# 1_-POWER.net
KiCad netlist of a schematic drawn in Altium Designer
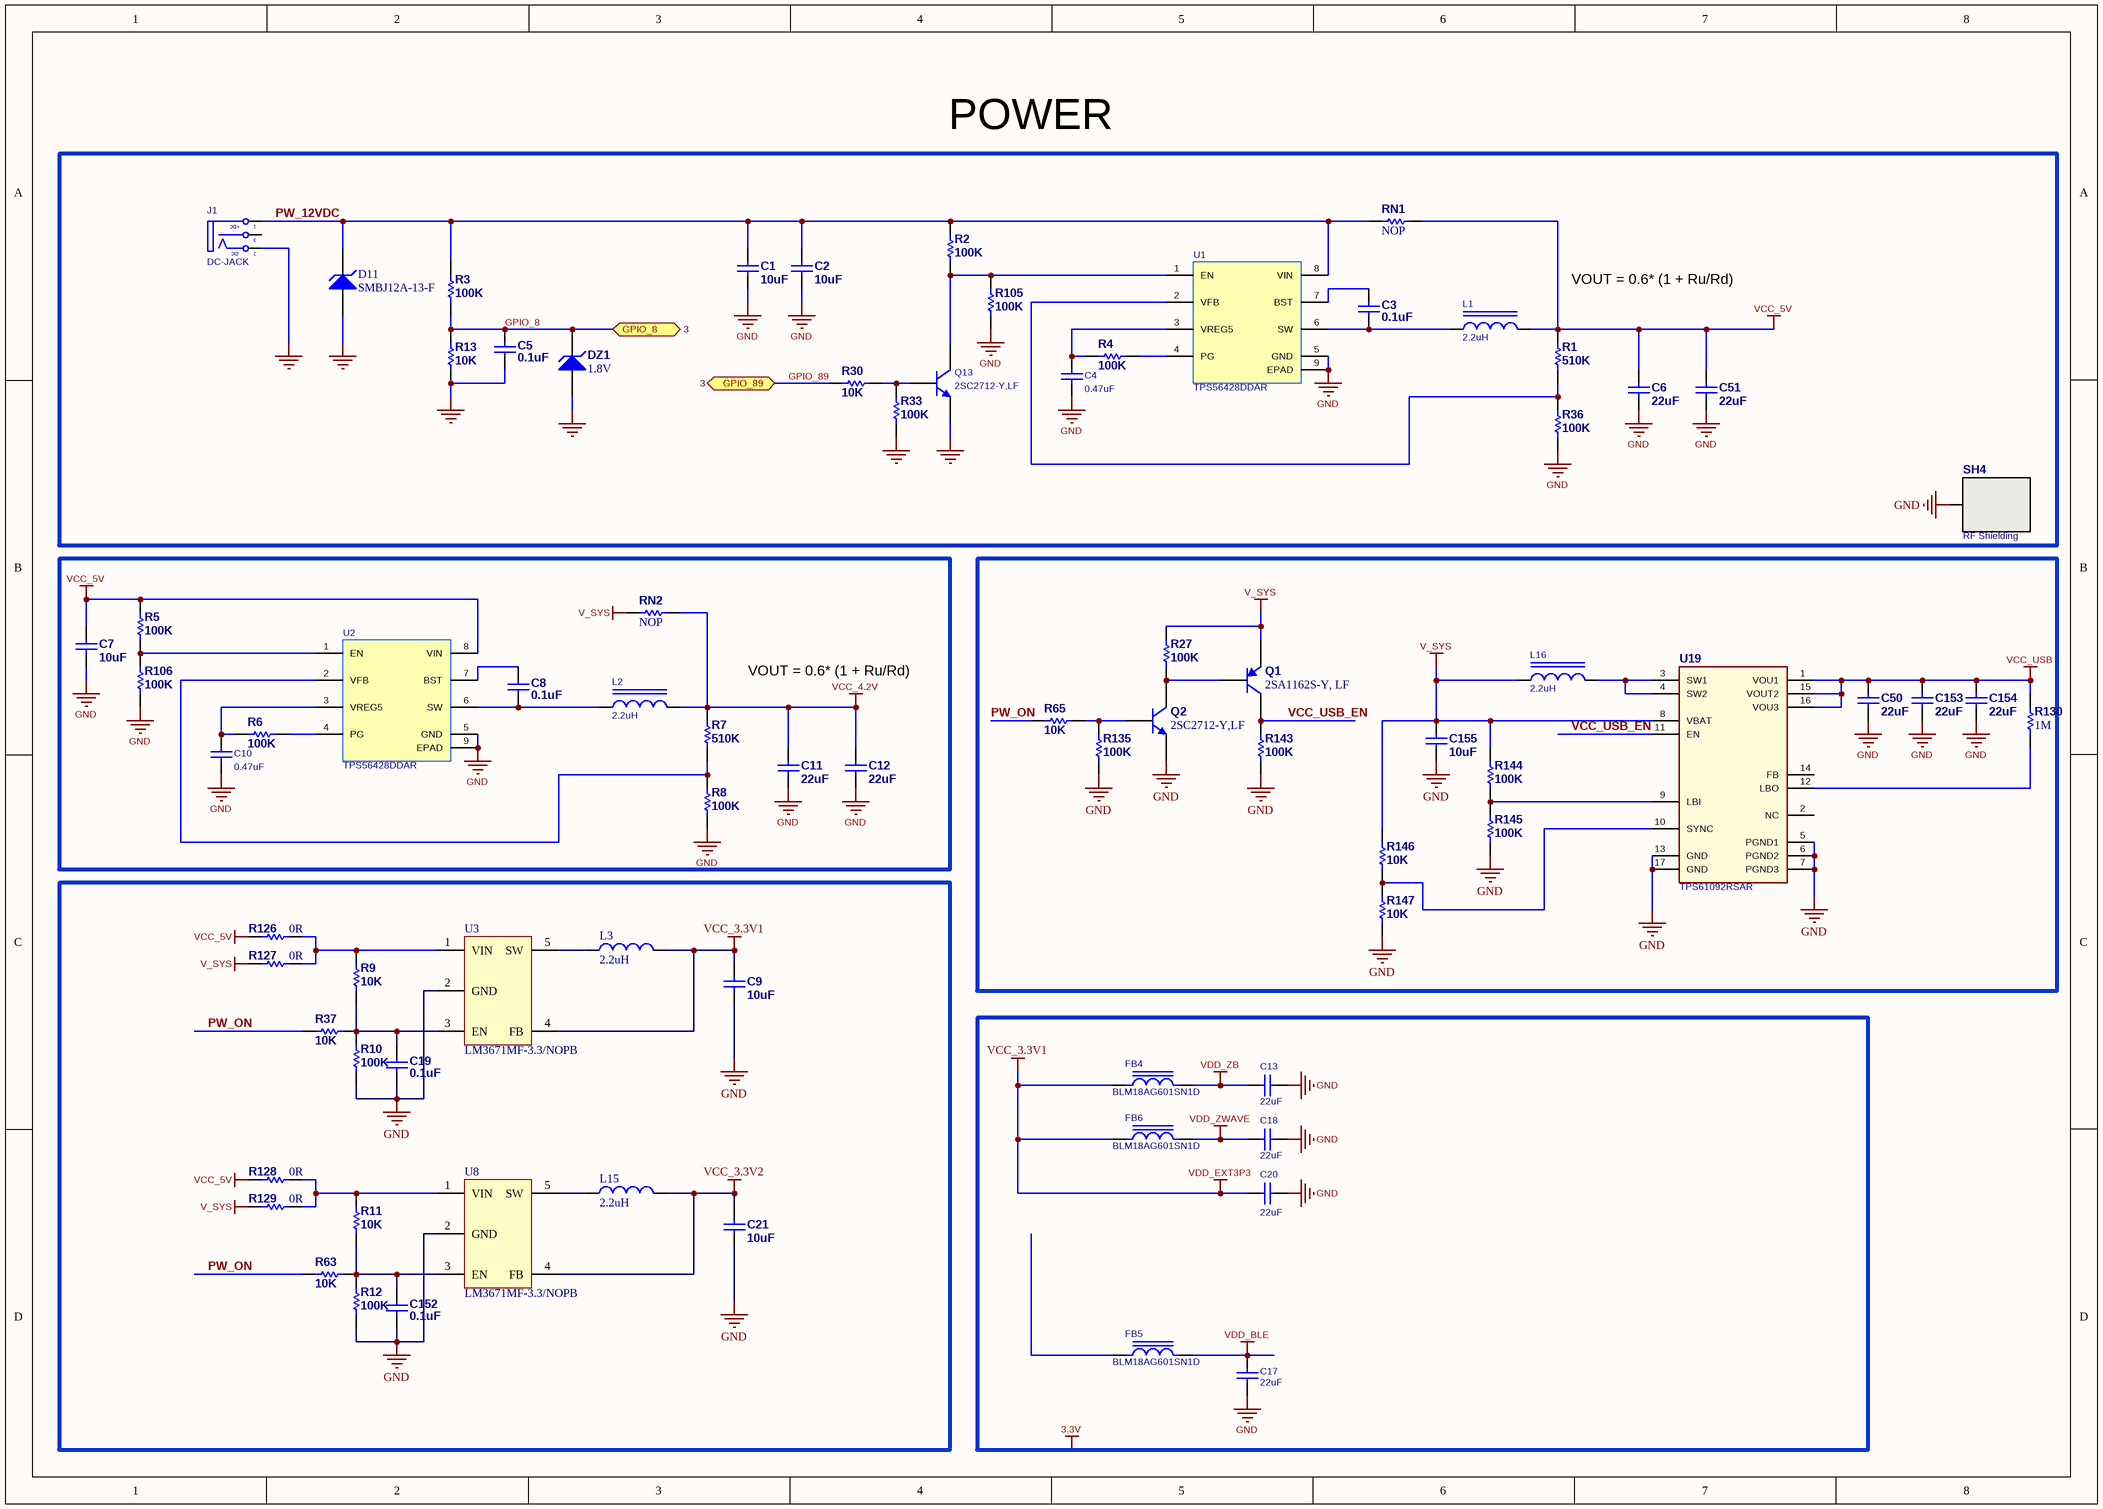
[diagram p0: [1]-POWER.SchDoc]

(export (version "E")
  (design (tool "Eeschema 10.0.6"))
  (components
    (comp (ref "C1")
      (value "TMK212BBJ106KG-T")
      (footprint "C0805")
      (description "CAP, CERM, 10uF, 25V, +/-10%, X5R, 0402")
      (fields
        (field (name "LUMI PART") "CAP_10uF_0805")
        (field (name "MANUFACTURER") "Taiyo Yuden")
        (field (name "CAPACITANCE") "10uF")
      )
      (libsource (lib "EFL_AltiumLib") (part "CAP_10uF_0805"))
    )
    (comp (ref "C2")
      (value "TMK212BBJ106KG-T")
      (footprint "C0805")
      (description "CAP, CERM, 10uF, 25V, +/-10%, X5R, 0402")
      (fields
        (field (name "LUMI PART") "CAP_10uF_0805")
        (field (name "MANUFACTURER") "Taiyo Yuden")
        (field (name "CAPACITANCE") "10uF")
      )
      (libsource (lib "EFL_AltiumLib") (part "CAP_10uF_0805"))
    )
    (comp (ref "C3")
      (value "0603B104K500CT")
      (footprint "C0603")
      (description "CAP, CERM, 0.1uF, 50V, +/-10%, X7R, 0603")
      (fields
        (field (name "LUMI PART") "CAP_104_0603")
        (field (name "MANUFACTURER") "Walsin")
        (field (name "CAPACITANCE") "0.1uF")
      )
      (libsource (lib "LumiLib-CAPACITOR") (part "CERM_0.1uF_0603"))
    )
    (comp (ref "C4")
      (value "0603B474K500CT")
      (footprint "C0603")
      (description "CAP, CERM, 0.47uF, 50V, +/-10%, X7R, 0603")
      (fields
        (field (name "LUMI PART") "CAP_0.47uF_0603")
        (field (name "MANUFACTURER") "Walsin")
        (field (name "CAPACITANCE") "0.47uF")
      )
      (libsource (lib "LumiLib-CAPACITOR") (part "CERM_0.47uF_0603"))
    )
    (comp (ref "C5")
      (value "0603B104K500CT")
      (footprint "C0603")
      (description "CAP, CERM, 0.1uF, 50V, +/-10%, X7R, 0603")
      (fields
        (field (name "LUMI PART") "CAP_104_0603")
        (field (name "MANUFACTURER") "Walsin")
        (field (name "CAPACITANCE") "0.1uF")
      )
      (libsource (lib "LumiLib-CAPACITOR") (part "CERM_0.1uF_0603"))
    )
    (comp (ref "C6")
      (value "0805X226M100CT")
      (footprint "C0805")
      (description "CAP, CERM, 22uF, 10V, +/-20%, X5R, 0805")
      (fields
        (field (name "LUMI PART") "CAP_22uF_0805")
        (field (name "MANUFACTURER") "Walsin")
        (field (name "CAPACITANCE") "22uF")
      )
      (libsource (lib "LumiLib-CAPACITOR") (part "CERM_22uF_0805"))
    )
    (comp (ref "C7")
      (value "TMK212BBJ106KG-T")
      (footprint "C0805")
      (description "CAP, CERM, 10uF, 25V, +/-10%, X5R, 0402")
      (fields
        (field (name "LUMI PART") "CAP_10uF_0805")
        (field (name "MANUFACTURER") "Taiyo Yuden")
        (field (name "CAPACITANCE") "10uF")
      )
      (libsource (lib "EFL_AltiumLib") (part "CAP_10uF_0805"))
    )
    (comp (ref "C8")
      (value "0603B104K500CT")
      (footprint "C0603")
      (description "CAP, CERM, 0.1uF, 50V, +/-10%, X7R, 0603")
      (fields
        (field (name "LUMI PART") "CAP_104_0603")
        (field (name "MANUFACTURER") "Walsin")
        (field (name "CAPACITANCE") "0.1uF")
      )
      (libsource (lib "LumiLib-CAPACITOR") (part "CERM_0.1uF_0603"))
    )
    (comp (ref "C9")
      (value "TMK212BBJ106KG-T")
      (footprint "C0805")
      (description "CAP, CERM, 10uF, 25V, +/-10%, X5R, 0402")
      (fields
        (field (name "LUMI PART") "CAP_10uF_0805")
        (field (name "MANUFACTURER") "Taiyo Yuden")
        (field (name "CAPACITANCE") "10uF")
      )
      (libsource (lib "EFL_AltiumLib") (part "CAP_10uF_0805"))
    )
    (comp (ref "C10")
      (value "0603B474K500CT")
      (footprint "C0603")
      (description "CAP, CERM, 0.47uF, 50V, +/-10%, X7R, 0603")
      (fields
        (field (name "LUMI PART") "CAP_0.47uF_0603")
        (field (name "MANUFACTURER") "Walsin")
        (field (name "CAPACITANCE") "0.47uF")
      )
      (libsource (lib "LumiLib-CAPACITOR") (part "CERM_0.47uF_0603"))
    )
    (comp (ref "C11")
      (value "0805X226M100CT")
      (footprint "C0805")
      (description "CAP, CERM, 22uF, 10V, +/-20%, X5R, 0805")
      (fields
        (field (name "LUMI PART") "CAP_22uF_0805")
        (field (name "MANUFACTURER") "Walsin")
        (field (name "CAPACITANCE") "22uF")
      )
      (libsource (lib "LumiLib-CAPACITOR") (part "CERM_22uF_0805"))
    )
    (comp (ref "C12")
      (value "0805X226M100CT")
      (footprint "C0805")
      (description "CAP, CERM, 22uF, 10V, +/-20%, X5R, 0805")
      (fields
        (field (name "LUMI PART") "CAP_22uF_0805")
        (field (name "MANUFACTURER") "Walsin")
        (field (name "CAPACITANCE") "22uF")
      )
      (libsource (lib "LumiLib-CAPACITOR") (part "CERM_22uF_0805"))
    )
    (comp (ref "C13")
      (value "0805X226M100CT")
      (footprint "C0805")
      (description "CAP, CERM, 22uF, 10V, +/-20%, X5R, 0805")
      (fields
        (field (name "TOLERANCE") "±20%")
        (field (name "LUMI PART") "CAP_22uF_0805")
        (field (name "CAPACITANCE") "22uF")
      )
      (libsource (lib "LumiLib-CAPACITOR") (part "CERM_22uF_0805"))
    )
    (comp (ref "C17")
      (value "0805X226M100CT")
      (footprint "C0805")
      (description "CAP, CERM, 22uF, 10V, +/-20%, X5R, 0805")
      (fields
        (field (name "TOLERANCE") "±20%")
        (field (name "LUMI PART") "CAP_22uF_0805")
        (field (name "CAPACITANCE") "22uF")
      )
      (libsource (lib "LumiLib-CAPACITOR") (part "CERM_22uF_0805"))
    )
    (comp (ref "C18")
      (value "0805X226M100CT")
      (footprint "C0805")
      (description "CAP, CERM, 22uF, 10V, +/-20%, X5R, 0805")
      (fields
        (field (name "TOLERANCE") "±20%")
        (field (name "LUMI PART") "CAP_22uF_0805")
        (field (name "CAPACITANCE") "22uF")
      )
      (libsource (lib "LumiLib-CAPACITOR") (part "CERM_22uF_0805"))
    )
    (comp (ref "C19")
      (value "0603B104K500CT")
      (footprint "C0603")
      (description "CAP, CERM, 0.1uF, 50V, +/-10%, X7R, 0603")
      (fields
        (field (name "LUMI PART") "CAP_104_0603")
        (field (name "MANUFACTURER") "Walsin")
        (field (name "CAPACITANCE") "0.1uF")
      )
      (libsource (lib "LumiLib-CAPACITOR") (part "CERM_0.1uF_0603"))
    )
    (comp (ref "C20")
      (value "0805X226M100CT")
      (footprint "C0805")
      (description "CAP, CERM, 22uF, 10V, +/-20%, X5R, 0805")
      (fields
        (field (name "TOLERANCE") "±20%")
        (field (name "LUMI PART") "CAP_22uF_0805")
        (field (name "CAPACITANCE") "22uF")
      )
      (libsource (lib "LumiLib-CAPACITOR") (part "CERM_22uF_0805"))
    )
    (comp (ref "C21")
      (value "TMK212BBJ106KG-T")
      (footprint "C0805")
      (description "CAP, CERM, 10uF, 25V, +/-10%, X5R, 0402")
      (fields
        (field (name "LUMI PART") "CAP_10uF_0805")
        (field (name "MANUFACTURER") "Taiyo Yuden")
        (field (name "CAPACITANCE") "10uF")
      )
      (libsource (lib "EFL_AltiumLib") (part "CAP_10uF_0805"))
    )
    (comp (ref "C50")
      (value "0805X226M100CT")
      (footprint "C0805")
      (description "CAP, CERM, 22uF, 10V, +/-20%, X5R, 0805")
      (fields
        (field (name "LUMI PART") "CAP_22uF_0805")
        (field (name "MANUFACTURER") "Walsin")
        (field (name "CAPACITANCE") "22uF")
      )
      (libsource (lib "LumiLib-CAPACITOR") (part "CERM_22uF_0805"))
    )
    (comp (ref "C51")
      (value "0805X226M100CT")
      (footprint "C0805")
      (description "CAP, CERM, 22uF, 10V, +/-20%, X5R, 0805")
      (fields
        (field (name "LUMI PART") "CAP_22uF_0805")
        (field (name "MANUFACTURER") "Walsin")
        (field (name "CAPACITANCE") "22uF")
      )
      (libsource (lib "LumiLib-CAPACITOR") (part "CERM_22uF_0805"))
    )
    (comp (ref "C152")
      (value "0603B104K500CT")
      (footprint "C0603")
      (description "CAP, CERM, 0.1uF, 50V, +/-10%, X7R, 0603")
      (fields
        (field (name "LUMI PART") "CAP_104_0603")
        (field (name "MANUFACTURER") "Walsin")
        (field (name "CAPACITANCE") "0.1uF")
      )
      (libsource (lib "LumiLib-CAPACITOR") (part "CERM_0.1uF_0603"))
    )
    (comp (ref "C153")
      (value "0805X226M100CT")
      (footprint "C0805")
      (description "CAP, CERM, 22uF, 10V, +/-20%, X5R, 0805")
      (fields
        (field (name "LUMI PART") "CAP_22uF_0805")
        (field (name "MANUFACTURER") "Walsin")
        (field (name "CAPACITANCE") "22uF")
      )
      (libsource (lib "LumiLib-CAPACITOR") (part "CERM_22uF_0805"))
    )
    (comp (ref "C154")
      (value "0805X226M100CT")
      (footprint "C0805")
      (description "CAP, CERM, 22uF, 10V, +/-20%, X5R, 0805")
      (fields
        (field (name "LUMI PART") "CAP_22uF_0805")
        (field (name "MANUFACTURER") "Walsin")
        (field (name "CAPACITANCE") "22uF")
      )
      (libsource (lib "LumiLib-CAPACITOR") (part "CERM_22uF_0805"))
    )
    (comp (ref "C155")
      (value "TMK212BBJ106KG-T")
      (footprint "C0805")
      (description "CAP, CERM, 10uF, 25V, +/-10%, X5R, 0402")
      (fields
        (field (name "LUMI PART") "CAP_10uF_0805")
        (field (name "MANUFACTURER") "Taiyo Yuden")
        (field (name "CAPACITANCE") "10uF")
      )
      (libsource (lib "EFL_AltiumLib") (part "CAP_10uF_0805"))
    )
    (comp (ref "D11")
      (value "SMBJ12A-13-F")
      (footprint "DO214AC")
      (description "ESD Suppressors / TVS Diodes 600W 12.0V")
      (fields
        (field (name "MANUFACTURER") "Diodes Incorporated")
        (field (name "LUMI PART") "DIODE_SMBJ12A-13-F")
        (field (name "MANUFACTURER PART NUMBER") "SMBJ12A-13-F")
      )
      (libsource (lib "VoiceControl") (part "SMBJ12A-13-F"))
    )
    (comp (ref "DZ1")
      (value "MMSZ5242BT1G")
      (footprint "SOD323")
      (description "DIODE, Zener, SOD-123, 500mW, 12V")
      (fields
        (field (name "MANUFACTURER") "Fairchild Semiconductor")
        (field (name "LUMI PART") "DIODE_MMSZ5242BT1G")
        (field (name "MAX. OPERATING VOLTAGE") "1.8V")
      )
      (libsource (lib "LumiLib-DIODE") (part "DIODE_MMSZ5242BT1G"))
    )
    (comp (ref "FB4")
      (value "BLM18AG601SN1D")
      (footprint "L0603")
      (description "EMI Filter Beads, 600 Ohms, 500mA, 0603")
      (fields
        (field (name "TOLERANCE") "±25%")
        (field (name "MANUFACTURER") "Murata")
        (field (name "MANUFACTURER PART NUMBER") "BLM18AG601SN1D")
      )
      (libsource (lib "LumiLib-INDUCTOR") (part "FB_BLM18AG601SN1D"))
    )
    (comp (ref "FB5")
      (value "BLM18AG601SN1D")
      (footprint "L0603")
      (description "EMI Filter Beads, 600 Ohms, 500mA, 0603")
      (fields
        (field (name "TOLERANCE") "±25%")
        (field (name "MANUFACTURER") "Murata")
        (field (name "MANUFACTURER PART NUMBER") "BLM18AG601SN1D")
      )
      (libsource (lib "LumiLib-INDUCTOR") (part "FB_BLM18AG601SN1D"))
    )
    (comp (ref "FB6")
      (value "BLM18AG601SN1D")
      (footprint "L0603")
      (description "EMI Filter Beads, 600 Ohms, 500mA, 0603")
      (fields
        (field (name "TOLERANCE") "±25%")
        (field (name "MANUFACTURER") "Murata")
        (field (name "MANUFACTURER PART NUMBER") "BLM18AG601SN1D")
      )
      (libsource (lib "LumiLib-INDUCTOR") (part "FB_BLM18AG601SN1D"))
    )
    (comp (ref "J1")
      (value "DC-JACK")
      (footprint "DC-IN")
      (description "Jac DC input")
      (libsource (lib "TuongPV") (part "DCIN"))
    )
    (comp (ref "L1")
      (value "SRP5020TA-2R2M")
      (footprint "SRP5020TA")
      (description "IND,5.7X5.2X1.8MM,2.2UH20%,4.2A")
      (fields (field (name "MANUFACTURER") "Bourns") (field (name "INDUCTANCE") "2.2uH"))
      (libsource (lib "TuongPV") (part "SRP5020TA-2R2M"))
    )
    (comp (ref "L2")
      (value "SRP5020TA-2R2M")
      (footprint "SRP5020TA")
      (description "IND,5.7X5.2X1.8MM,2.2UH20%,4.2A")
      (fields (field (name "MANUFACTURER") "Bourns") (field (name "INDUCTANCE") "2.2uH"))
      (libsource (lib "TuongPV") (part "SRP5020TA-2R2M"))
    )
    (comp (ref "L3")
      (value "BRL3225T2R2M")
      (footprint "L1210")
      (description "Fixed Inductors 10uH")
      (fields
        (field (name "TOLERANCE") "±20%")
        (field (name "MANUFACTURER") "Taiyo Yuden")
        (field (name "INDUCTANCE") "2.2uH")
      )
      (libsource (lib "VoiceControl") (part "BRL3225T2R2M"))
    )
    (comp (ref "L15")
      (value "BRL3225T2R2M")
      (footprint "L1210")
      (description "Fixed Inductors 10uH")
      (fields
        (field (name "TOLERANCE") "±20%")
        (field (name "MANUFACTURER") "Taiyo Yuden")
        (field (name "INDUCTANCE") "2.2uH")
      )
      (libsource (lib "VoiceControl") (part "BRL3225T2R2M"))
    )
    (comp (ref "L16")
      (value "SRP5020TA-2R2M")
      (footprint "SRP5020TA")
      (description "IND,5.7X5.2X1.8MM,2.2UH20%,4.2A")
      (fields (field (name "MANUFACTURER") "Bourns") (field (name "INDUCTANCE") "2.2uH"))
      (libsource (lib "TuongPV") (part "SRP5020TA-2R2M"))
    )
    (comp (ref "Q1")
      (value "2SA1162S-Y, LF")
      (footprint "SOT23-3")
      (description "TRANS, PNP, 50V, 0.15A, SOT-23-3")
      (fields
        (field (name "MANUFACTURER") "Toshiba")
        (field (name "LUMI PART") "TRANS_BC807")
        (field (name "MANUFACTURER PART NUMBER") "2SA1162S-Y, LF")
      )
      (libsource (lib "LumiLib_TRANSISTOR") (part "TRANS_2SA1162-Y"))
    )
    (comp (ref "Q2")
      (value "2SC2712-Y,LF")
      (footprint "SOT23-3")
      (description "TRANS, NPN, 50V, 0.15A, SOT-23-3")
      (fields
        (field (name "MANUFACTURER") "Toshiba")
        (field (name "LUMI PART") "TRANS_MMBT3904")
        (field (name "MANUFACTURER PART NUMBER") "2SC2712-Y,LF")
      )
      (libsource (lib "LumiLib_TRANSISTOR") (part "TRANS_SC2712-Y"))
    )
    (comp (ref "Q13")
      (value "2SC2712-Y,LF")
      (footprint "SOT_23_TO_236AB_REFLOW")
      (description "TRANS, NPN, 50V, 0.15A, SOT-23-3")
      (fields
        (field (name "MANUFACTURER") "Toshiba")
        (field (name "LUMI PART") "TRANS_MMBT3904")
        (field (name "MANUFACTURER PART NUMBER") "2SC2712-Y,LF")
      )
      (libsource (lib "LumiLib_TRANSISTOR") (part "TRANS_SC2712-Y"))
    )
    (comp (ref "R1")
      (value "RC0603FR-07510KL")
      (footprint "R0603")
      (description "Thick Film Resistors 510K OHM 1%")
      (fields
        (field (name "MANUFACTURER") "Yageo")
        (field (name "LUMI PART") "RES_510K_0603")
        (field (name "RESISTANCE (OHMS)") "510K")
      )
      (libsource (lib "EFL_GW") (part "RES_510K_0603"))
    )
    (comp (ref "R2")
      (value "WR06X1003 FTL")
      (footprint "R0603")
      (description "RES, SMD, ThickFilm, 100K, 1/10W, 1%, 0603")
      (fields
        (field (name "MANUFACTURER") "Walsin")
        (field (name "LUMI PART") "RES_100K_0603")
        (field (name "RESISTANCE (OHMS)") "100K")
      )
      (libsource (lib "LumiLib-RESISTOR") (part "RES_100K_0603"))
    )
    (comp (ref "R3")
      (value "WR06X1003 FTL")
      (footprint "R0603")
      (description "RES, SMD, ThickFilm, 100K, 1/10W, 1%, 0603")
      (fields
        (field (name "MANUFACTURER") "Walsin")
        (field (name "LUMI PART") "RES_100K_0603")
        (field (name "RESISTANCE (OHMS)") "100K")
      )
      (libsource (lib "LumiLib-RESISTOR") (part "RES_100K_0603"))
    )
    (comp (ref "R4")
      (value "WR06X1003 FTL")
      (footprint "R0603")
      (description "RES, SMD, ThickFilm, 100K, 1/10W, 1%, 0603")
      (fields
        (field (name "MANUFACTURER") "Walsin")
        (field (name "LUMI PART") "RES_100K_0603")
        (field (name "RESISTANCE (OHMS)") "100K")
      )
      (libsource (lib "LumiLib-RESISTOR") (part "RES_100K_0603"))
    )
    (comp (ref "R5")
      (value "WR06X1003 FTL")
      (footprint "R0603")
      (description "RES, SMD, ThickFilm, 100K, 1/10W, 1%, 0603")
      (fields
        (field (name "MANUFACTURER") "Walsin")
        (field (name "LUMI PART") "RES_100K_0603")
        (field (name "RESISTANCE (OHMS)") "100K")
      )
      (libsource (lib "LumiLib-RESISTOR") (part "RES_100K_0603"))
    )
    (comp (ref "R6")
      (value "WR06X1003 FTL")
      (footprint "R0603")
      (description "RES, SMD, ThickFilm, 100K, 1/10W, 1%, 0603")
      (fields
        (field (name "MANUFACTURER") "Walsin")
        (field (name "LUMI PART") "RES_100K_0603")
        (field (name "RESISTANCE (OHMS)") "100K")
      )
      (libsource (lib "LumiLib-RESISTOR") (part "RES_100K_0603"))
    )
    (comp (ref "R7")
      (value "RC0603FR-07510KL")
      (footprint "R0603")
      (description "Thick Film Resistors 510K OHM 1%")
      (fields
        (field (name "MANUFACTURER") "Yageo")
        (field (name "LUMI PART") "RES_510K_0603")
        (field (name "RESISTANCE (OHMS)") "510K")
      )
      (libsource (lib "EFL_GW") (part "RES_510K_0603"))
    )
    (comp (ref "R8")
      (value "WR06X1003 FTL")
      (footprint "R0603")
      (description "RES, SMD, ThickFilm, 100K, 1/10W, 1%, 0603")
      (fields
        (field (name "MANUFACTURER") "Walsin")
        (field (name "LUMI PART") "RES_100K_0603")
        (field (name "RESISTANCE (OHMS)") "100K")
      )
      (libsource (lib "LumiLib-RESISTOR") (part "RES_100K_0603"))
    )
    (comp (ref "R9")
      (value "WR06X103 JTL")
      (footprint "R0603")
      (description "RES, SMD, ThickFilm, 10K, 1/10W, 5%, 0603")
      (fields
        (field (name "MANUFACTURER") "Walsin")
        (field (name "LUMI PART") "RES_10K_0603")
        (field (name "RESISTANCE (OHMS)") "10K")
      )
      (libsource (lib "LumiLib-RESISTOR") (part "RES_10K_0603"))
    )
    (comp (ref "R10")
      (value "WR06X1003 FTL")
      (footprint "R0603")
      (description "RES, SMD, ThickFilm, 100K, 1/10W, 1%, 0603")
      (fields
        (field (name "MANUFACTURER") "Walsin")
        (field (name "LUMI PART") "RES_100K_0603")
        (field (name "RESISTANCE (OHMS)") "100K")
      )
      (libsource (lib "LumiLib-RESISTOR") (part "RES_100K_0603"))
    )
    (comp (ref "R11")
      (value "WR06X103 JTL")
      (footprint "R0603")
      (description "RES, SMD, ThickFilm, 10K, 1/10W, 5%, 0603")
      (fields
        (field (name "MANUFACTURER") "Walsin")
        (field (name "LUMI PART") "RES_10K_0603")
        (field (name "RESISTANCE (OHMS)") "10K")
      )
      (libsource (lib "LumiLib-RESISTOR") (part "RES_10K_0603"))
    )
    (comp (ref "R12")
      (value "WR06X1003 FTL")
      (footprint "R0603")
      (description "RES, SMD, ThickFilm, 100K, 1/10W, 1%, 0603")
      (fields
        (field (name "MANUFACTURER") "Walsin")
        (field (name "LUMI PART") "RES_100K_0603")
        (field (name "RESISTANCE (OHMS)") "100K")
      )
      (libsource (lib "LumiLib-RESISTOR") (part "RES_100K_0603"))
    )
    (comp (ref "R13")
      (value "WR06X103 JTL")
      (footprint "R0603")
      (description "RES, SMD, ThickFilm, 10K, 1/10W, 5%, 0603")
      (fields
        (field (name "MANUFACTURER") "Walsin")
        (field (name "LUMI PART") "RES_10K_0603")
        (field (name "RESISTANCE (OHMS)") "10K")
      )
      (libsource (lib "LumiLib-RESISTOR") (part "RES_10K_0603"))
    )
    (comp (ref "R27")
      (value "WR06X1003 FTL")
      (footprint "R0603")
      (description "RES, SMD, ThickFilm, 100K, 1/10W, 1%, 0603")
      (fields
        (field (name "MANUFACTURER") "Walsin")
        (field (name "LUMI PART") "RES_100K_0603")
        (field (name "RESISTANCE (OHMS)") "100K")
      )
      (libsource (lib "LumiLib-RESISTOR") (part "RES_100K_0603"))
    )
    (comp (ref "R30")
      (value "WR06X103 JTL")
      (footprint "R0603")
      (description "RES, SMD, ThickFilm, 10K, 1/10W, 5%, 0603")
      (fields
        (field (name "MANUFACTURER") "Walsin")
        (field (name "LUMI PART") "RES_10K_0603")
        (field (name "RESISTANCE (OHMS)") "10K")
      )
      (libsource (lib "LumiLib-RESISTOR") (part "RES_10K_0603"))
    )
    (comp (ref "R33")
      (value "WR06X1003 FTL")
      (footprint "R0603")
      (description "RES, SMD, ThickFilm, 100K, 1/10W, 1%, 0603")
      (fields
        (field (name "MANUFACTURER") "Walsin")
        (field (name "LUMI PART") "RES_100K_0603")
        (field (name "RESISTANCE (OHMS)") "100K")
      )
      (libsource (lib "LumiLib-RESISTOR") (part "RES_100K_0603"))
    )
    (comp (ref "R36")
      (value "WR06X1003 FTL")
      (footprint "R0603")
      (description "RES, SMD, ThickFilm, 100K, 1/10W, 1%, 0603")
      (fields
        (field (name "MANUFACTURER") "Walsin")
        (field (name "LUMI PART") "RES_100K_0603")
        (field (name "RESISTANCE (OHMS)") "100K")
      )
      (libsource (lib "LumiLib-RESISTOR") (part "RES_100K_0603"))
    )
    (comp (ref "R37")
      (value "WR06X103 JTL")
      (footprint "R0603")
      (description "RES, SMD, ThickFilm, 10K, 1/10W, 5%, 0603")
      (fields
        (field (name "MANUFACTURER") "Walsin")
        (field (name "LUMI PART") "RES_10K_0603")
        (field (name "RESISTANCE (OHMS)") "10K")
      )
      (libsource (lib "LumiLib-RESISTOR") (part "RES_10K_0603"))
    )
    (comp (ref "R63")
      (value "WR06X103 JTL")
      (footprint "R0603")
      (description "RES, SMD, ThickFilm, 10K, 1/10W, 5%, 0603")
      (fields
        (field (name "MANUFACTURER") "Walsin")
        (field (name "LUMI PART") "RES_10K_0603")
        (field (name "RESISTANCE (OHMS)") "10K")
      )
      (libsource (lib "LumiLib-RESISTOR") (part "RES_10K_0603"))
    )
    (comp (ref "R65")
      (value "WR06X103 JTL")
      (footprint "R0603")
      (description "RES, SMD, ThickFilm, 10K, 1/10W, 5%, 0603")
      (fields
        (field (name "MANUFACTURER") "Walsin")
        (field (name "LUMI PART") "RES_10K_0603")
        (field (name "RESISTANCE (OHMS)") "10K")
      )
      (libsource (lib "LumiLib-RESISTOR") (part "RES_10K_0603"))
    )
    (comp (ref "R105")
      (value "WR06X1003 FTL")
      (footprint "R0603")
      (description "RES, SMD, ThickFilm, 100K, 1/10W, 1%, 0603")
      (fields
        (field (name "MANUFACTURER") "Walsin")
        (field (name "LUMI PART") "RES_100K_0603")
        (field (name "RESISTANCE (OHMS)") "100K")
      )
      (libsource (lib "LumiLib-RESISTOR") (part "RES_100K_0603"))
    )
    (comp (ref "R106")
      (value "WR06X1003 FTL")
      (footprint "R0603")
      (description "RES, SMD, ThickFilm, 100K, 1/10W, 1%, 0603")
      (fields
        (field (name "MANUFACTURER") "Walsin")
        (field (name "LUMI PART") "RES_100K_0603")
        (field (name "RESISTANCE (OHMS)") "100K")
      )
      (libsource (lib "LumiLib-RESISTOR") (part "RES_100K_0603"))
    )
    (comp (ref "R126")
      (value "WR06X000 PTL")
      (footprint "R0603")
      (description "RES, SMD, ThickFilm, 0R, JUMPER, 0603")
      (fields
        (field (name "MANUFACTURER") "Walsin")
        (field (name "LUMI PART") "RES_0R_0603")
        (field (name "RESISTANCE (OHMS)") "0R")
      )
      (libsource (lib "LumiLib-RESISTOR") (part "RES_0R_0603"))
    )
    (comp (ref "R127")
      (value "WR06X000 PTL")
      (footprint "R0603")
      (description "RES, SMD, ThickFilm, 0R, JUMPER, 0603")
      (fields
        (field (name "MANUFACTURER") "Walsin")
        (field (name "LUMI PART") "RES_0R_0603")
        (field (name "RESISTANCE (OHMS)") "0R")
      )
      (libsource (lib "LumiLib-RESISTOR") (part "RES_0R_0603"))
    )
    (comp (ref "R128")
      (value "WR06X000 PTL")
      (footprint "R0603")
      (description "RES, SMD, ThickFilm, 0R, JUMPER, 0603")
      (fields
        (field (name "MANUFACTURER") "Walsin")
        (field (name "LUMI PART") "RES_0R_0603")
        (field (name "RESISTANCE (OHMS)") "0R")
      )
      (libsource (lib "LumiLib-RESISTOR") (part "RES_0R_0603"))
    )
    (comp (ref "R129")
      (value "WR06X000 PTL")
      (footprint "R0603")
      (description "RES, SMD, ThickFilm, 0R, JUMPER, 0603")
      (fields
        (field (name "MANUFACTURER") "Walsin")
        (field (name "LUMI PART") "RES_0R_0603")
        (field (name "RESISTANCE (OHMS)") "0R")
      )
      (libsource (lib "LumiLib-RESISTOR") (part "RES_0R_0603"))
    )
    (comp (ref "R130")
      (value "WR06X105 FTL")
      (footprint "R0603")
      (description "RES, SMD, ThickFilm, 1M, 1/10W, 1%, 0603")
      (fields
        (field (name "MANUFACTURER") "Walsin")
        (field (name "LUMI PART") "RES_1M_0603")
        (field (name "RESISTANCE (OHMS)") "1M")
      )
      (libsource (lib "LumiLib-RESISTOR") (part "RES_1M_0603"))
    )
    (comp (ref "R135")
      (value "WR06X1003 FTL")
      (footprint "R0603")
      (description "RES, SMD, ThickFilm, 100K, 1/10W, 1%, 0603")
      (fields
        (field (name "MANUFACTURER") "Walsin")
        (field (name "LUMI PART") "RES_100K_0603")
        (field (name "RESISTANCE (OHMS)") "100K")
      )
      (libsource (lib "LumiLib-RESISTOR") (part "RES_100K_0603"))
    )
    (comp (ref "R143")
      (value "WR06X1003 FTL")
      (footprint "R0603")
      (description "RES, SMD, ThickFilm, 100K, 1/10W, 1%, 0603")
      (fields
        (field (name "MANUFACTURER") "Walsin")
        (field (name "LUMI PART") "RES_100K_0603")
        (field (name "RESISTANCE (OHMS)") "100K")
      )
      (libsource (lib "LumiLib-RESISTOR") (part "RES_100K_0603"))
    )
    (comp (ref "R144")
      (value "WR06X1003 FTL")
      (footprint "R0603")
      (description "RES, SMD, ThickFilm, 100K, 1/10W, 1%, 0603")
      (fields
        (field (name "MANUFACTURER") "Walsin")
        (field (name "LUMI PART") "RES_100K_0603")
        (field (name "RESISTANCE (OHMS)") "100K")
      )
      (libsource (lib "LumiLib-RESISTOR") (part "RES_100K_0603"))
    )
    (comp (ref "R145")
      (value "WR06X1003 FTL")
      (footprint "R0603")
      (description "RES, SMD, ThickFilm, 100K, 1/10W, 1%, 0603")
      (fields
        (field (name "MANUFACTURER") "Walsin")
        (field (name "LUMI PART") "RES_100K_0603")
        (field (name "RESISTANCE (OHMS)") "100K")
      )
      (libsource (lib "LumiLib-RESISTOR") (part "RES_100K_0603"))
    )
    (comp (ref "R146")
      (value "WR06X103 JTL")
      (footprint "R0603")
      (description "RES, SMD, ThickFilm, 10K, 1/10W, 5%, 0603")
      (fields
        (field (name "MANUFACTURER") "Walsin")
        (field (name "LUMI PART") "RES_10K_0603")
        (field (name "RESISTANCE (OHMS)") "10K")
      )
      (libsource (lib "LumiLib-RESISTOR") (part "RES_10K_0603"))
    )
    (comp (ref "R147")
      (value "WR06X103 JTL")
      (footprint "R0603")
      (description "RES, SMD, ThickFilm, 10K, 1/10W, 5%, 0603")
      (fields
        (field (name "MANUFACTURER") "Walsin")
        (field (name "LUMI PART") "RES_10K_0603")
        (field (name "RESISTANCE (OHMS)") "10K")
      )
      (libsource (lib "LumiLib-RESISTOR") (part "RES_10K_0603"))
    )
    (comp (ref "RN1")
      (value "WR12X000 PTL")
      (footprint "R1206")
      (description "RES, SMD, ThickFilm, 0R, JUMPER, 1206")
      (fields
        (field (name "MANUFACTURER") "Walsin")
        (field (name "LUMI PART") "RES_0R_1206")
        (field (name "RESISTANCE (OHMS)") "NOP")
      )
      (libsource (lib "LumiLib-RESISTOR") (part "RES_0R_1206"))
    )
    (comp (ref "RN2")
      (value "WR12X000 PTL")
      (footprint "R1206")
      (description "RES, SMD, ThickFilm, 0R, JUMPER, 1206")
      (fields
        (field (name "MANUFACTURER") "Walsin")
        (field (name "LUMI PART") "RES_0R_1206")
        (field (name "RESISTANCE (OHMS)") "NOP")
      )
      (libsource (lib "LumiLib-RESISTOR") (part "RES_0R_1206"))
    )
    (comp (ref "SH4")
      (value "RF Shielding")
      (footprint "RFSHIELD_34x37")
      (libsource (lib "EFL_GW") (part "RF_SHIELDING"))
    )
    (comp (ref "U1")
      (value "TPS56428DDAR")
      (footprint "SOP8-PAD")
      (description "IC REG BUCK ADJUSTABLE 4A 8SOPWR")
      (libsource (lib "TuongPV") (part "TPS56428DDAR"))
    )
    (comp (ref "U2")
      (value "TPS56428DDAR")
      (footprint "SOP8-PAD")
      (description "IC REG BUCK ADJUSTABLE 4A 8SOPWR")
      (libsource (lib "TuongPV") (part "TPS56428DDAR"))
    )
    (comp (ref "U3")
      (value "LM3671MF-3.3/NOPB")
      (footprint "SOT23-5")
      (description "Switching Voltage Regulators 2MHZ,600MA STEP-DOWN DC-DC CONVERTER")
      (fields
        (field (name "MANUFACTURER") "Texas Instruments")
        (field (name "LUMI PART") "LM3671MF-3.3/NOPB")
      )
      (libsource (lib "VoiceControl") (part "LM3671MF-3.3/NOPB"))
    )
    (comp (ref "U8")
      (value "LM3671MF-3.3/NOPB")
      (footprint "SOT23-5")
      (description "Switching Voltage Regulators 2MHZ,600MA STEP-DOWN DC-DC CONVERTER")
      (fields
        (field (name "MANUFACTURER") "Texas Instruments")
        (field (name "LUMI PART") "LM3671MF-3.3/NOPB")
      )
      (libsource (lib "VoiceControl") (part "LM3671MF-3.3/NOPB"))
    )
    (comp (ref "U19")
      (value "TPS61092RSAR")
      (footprint "QFN16-4x4x0.7-0.65")
      (description "IC REG BOOST 5V 2A 16QFN")
      (fields (field (name "MANUFACTURER") "TI") (field (name "MANUFACTURER PART NUMBER") "TPS61092RSAR"))
      (libsource (lib "EFL_GW") (part "TPS61092RSAR"))
    )
  )
  (nets
    (net (code "1") (name "/GPIO_8") (class "Default")
      (node (ref "C5") (pin "2") (pinfunction "2_2") (pintype "passive"))
      (node (ref "DZ1") (pin "2") (pinfunction "K_2") (pintype "passive"))
      (node (ref "R13") (pin "2") (pinfunction "2_2") (pintype "passive"))
      (node (ref "R3") (pin "1") (pinfunction "1_1") (pintype "passive"))
    )
    (net (code "2") (name "/GPIO_89") (class "Default")
      (node (ref "R30") (pin "2") (pinfunction "2_2") (pintype "passive"))
    )
    (net (code "3") (name "/PW_12VDC") (class "Default")
      (node (ref "C1") (pin "2") (pinfunction "2_2") (pintype "passive"))
      (node (ref "C2") (pin "2") (pinfunction "2_2") (pintype "passive"))
      (node (ref "D11") (pin "2") (pinfunction "K_2") (pintype "passive"))
      (node (ref "J1") (pin "1") (pinfunction "T_1") (pintype "passive"))
      (node (ref "R2") (pin "2") (pinfunction "2_2") (pintype "passive"))
      (node (ref "R3") (pin "2") (pinfunction "2_2") (pintype "passive"))
      (node (ref "RN1") (pin "1") (pinfunction "1_1") (pintype "passive"))
      (node (ref "U1") (pin "8") (pinfunction "VIN_8") (pintype "passive"))
    )
    (net (code "4") (name "/PW_ON") (class "Default")
      (node (ref "R37") (pin "2") (pinfunction "2_2") (pintype "passive"))
      (node (ref "R63") (pin "2") (pinfunction "2_2") (pintype "passive"))
      (node (ref "R65") (pin "1") (pinfunction "1_1") (pintype "passive"))
    )
    (net (code "5") (name "/VCC_USB_EN") (class "Default")
      (node (ref "Q1") (pin "3") (pinfunction "C_3") (pintype "passive"))
      (node (ref "R143") (pin "1") (pinfunction "1_1") (pintype "passive"))
      (node (ref "U19") (pin "11") (pinfunction "EN_11") (pintype "passive"))
    )
    (net (code "7") (name "GND") (class "Default")
      (node (ref "C1") (pin "1") (pinfunction "1_1") (pintype "passive"))
      (node (ref "C10") (pin "1") (pinfunction "1_1") (pintype "passive"))
      (node (ref "C11") (pin "1") (pinfunction "1_1") (pintype "passive"))
      (node (ref "C12") (pin "1") (pinfunction "1_1") (pintype "passive"))
      (node (ref "C13") (pin "1") (pinfunction "1_1") (pintype "passive"))
      (node (ref "C152") (pin "1") (pinfunction "1_1") (pintype "passive"))
      (node (ref "C153") (pin "1") (pinfunction "1_1") (pintype "passive"))
      (node (ref "C154") (pin "1") (pinfunction "1_1") (pintype "passive"))
      (node (ref "C155") (pin "1") (pinfunction "1_1") (pintype "passive"))
      (node (ref "C17") (pin "2") (pinfunction "2_2") (pintype "passive"))
      (node (ref "C18") (pin "2") (pinfunction "2_2") (pintype "passive"))
      (node (ref "C19") (pin "1") (pinfunction "1_1") (pintype "passive"))
      (node (ref "C2") (pin "1") (pinfunction "1_1") (pintype "passive"))
      (node (ref "C20") (pin "1") (pinfunction "1_1") (pintype "passive"))
      (node (ref "C21") (pin "1") (pinfunction "1_1") (pintype "passive"))
      (node (ref "C4") (pin "1") (pinfunction "1_1") (pintype "passive"))
      (node (ref "C5") (pin "1") (pinfunction "1_1") (pintype "passive"))
      (node (ref "C50") (pin "1") (pinfunction "1_1") (pintype "passive"))
      (node (ref "C51") (pin "1") (pinfunction "1_1") (pintype "passive"))
      (node (ref "C6") (pin "1") (pinfunction "1_1") (pintype "passive"))
      (node (ref "C7") (pin "1") (pinfunction "1_1") (pintype "passive"))
      (node (ref "C9") (pin "1") (pinfunction "1_1") (pintype "passive"))
      (node (ref "D11") (pin "1") (pinfunction "A_1") (pintype "passive"))
      (node (ref "DZ1") (pin "1") (pinfunction "A_1") (pintype "passive"))
      (node (ref "J1") (pin "2") (pinfunction "TN_2") (pintype "passive"))
      (node (ref "Q13") (pin "2") (pinfunction "E_2") (pintype "passive"))
      (node (ref "Q2") (pin "2") (pinfunction "E_2") (pintype "passive"))
      (node (ref "R10") (pin "2") (pinfunction "2_2") (pintype "passive"))
      (node (ref "R105") (pin "1") (pinfunction "1_1") (pintype "passive"))
      (node (ref "R106") (pin "1") (pinfunction "1_1") (pintype "passive"))
      (node (ref "R12") (pin "2") (pinfunction "2_2") (pintype "passive"))
      (node (ref "R13") (pin "1") (pinfunction "1_1") (pintype "passive"))
      (node (ref "R135") (pin "2") (pinfunction "2_2") (pintype "passive"))
      (node (ref "R143") (pin "2") (pinfunction "2_2") (pintype "passive"))
      (node (ref "R145") (pin "2") (pinfunction "2_2") (pintype "passive"))
      (node (ref "R147") (pin "2") (pinfunction "2_2") (pintype "passive"))
      (node (ref "R33") (pin "1") (pinfunction "1_1") (pintype "passive"))
      (node (ref "R36") (pin "2") (pinfunction "2_2") (pintype "passive"))
      (node (ref "R8") (pin "2") (pinfunction "2_2") (pintype "passive"))
      (node (ref "SH4") (pin "1") (pinfunction "1_1") (pintype "passive"))
      (node (ref "U1") (pin "5") (pinfunction "GND_5") (pintype "passive"))
      (node (ref "U1") (pin "9") (pinfunction "EPAD_9") (pintype "passive"))
      (node (ref "U19") (pin "13") (pinfunction "GND_13") (pintype "passive"))
      (node (ref "U19") (pin "17") (pinfunction "GND_17") (pintype "passive"))
      (node (ref "U19") (pin "5") (pinfunction "PGND1_5") (pintype "passive"))
      (node (ref "U19") (pin "6") (pinfunction "PGND2_6") (pintype "passive"))
      (node (ref "U19") (pin "7") (pinfunction "PGND3_7") (pintype "passive"))
      (node (ref "U2") (pin "5") (pinfunction "GND_5") (pintype "passive"))
      (node (ref "U2") (pin "9") (pinfunction "EPAD_9") (pintype "passive"))
      (node (ref "U3") (pin "2") (pinfunction "GND_2") (pintype "passive"))
      (node (ref "U8") (pin "2") (pinfunction "GND_2") (pintype "passive"))
    )
    (net (code "8") (name "Net-(Q1-B)") (class "Default")
      (node (ref "Q1") (pin "1") (pinfunction "B_1") (pintype "passive"))
      (node (ref "Q2") (pin "3") (pinfunction "C_3") (pintype "passive"))
      (node (ref "R27") (pin "2") (pinfunction "2_2") (pintype "passive"))
    )
    (net (code "9") (name "Net-(Q2-B)") (class "Default")
      (node (ref "Q2") (pin "1") (pinfunction "B_1") (pintype "passive"))
      (node (ref "R135") (pin "1") (pinfunction "1_1") (pintype "passive"))
      (node (ref "R65") (pin "2") (pinfunction "2_2") (pintype "passive"))
    )
    (net (code "10") (name "Net-(Q13-B)") (class "Default")
      (node (ref "Q13") (pin "1") (pinfunction "B_1") (pintype "passive"))
      (node (ref "R30") (pin "1") (pinfunction "1_1") (pintype "passive"))
      (node (ref "R33") (pin "2") (pinfunction "2_2") (pintype "passive"))
    )
    (net (code "11") (name "Net-(Q13-C)") (class "Default")
      (node (ref "Q13") (pin "3") (pinfunction "C_3") (pintype "passive"))
      (node (ref "R105") (pin "2") (pinfunction "2_2") (pintype "passive"))
      (node (ref "R2") (pin "1") (pinfunction "1_1") (pintype "passive"))
      (node (ref "U1") (pin "1") (pinfunction "EN_1") (pintype "passive"))
    )
    (net (code "12") (name "Net-(U1-BST)") (class "Default")
      (node (ref "C3") (pin "2") (pinfunction "2_2") (pintype "passive"))
      (node (ref "U1") (pin "7") (pinfunction "BST_7") (pintype "passive"))
    )
    (net (code "13") (name "Net-(U1-PG)") (class "Default")
      (node (ref "R4") (pin "1") (pinfunction "1_1") (pintype "passive"))
      (node (ref "U1") (pin "4") (pinfunction "PG_4") (pintype "passive"))
    )
    (net (code "14") (name "Net-(U1-SW)") (class "Default")
      (node (ref "C3") (pin "1") (pinfunction "1_1") (pintype "passive"))
      (node (ref "L1") (pin "1") (pinfunction "1_1") (pintype "passive"))
      (node (ref "U1") (pin "6") (pinfunction "SW_6") (pintype "passive"))
    )
    (net (code "15") (name "Net-(U1-VFB)") (class "Default")
      (node (ref "R1") (pin "2") (pinfunction "2_2") (pintype "passive"))
      (node (ref "R36") (pin "1") (pinfunction "1_1") (pintype "passive"))
      (node (ref "U1") (pin "2") (pinfunction "VFB_2") (pintype "passive"))
    )
    (net (code "16") (name "Net-(U1-VREG5)") (class "Default")
      (node (ref "C4") (pin "2") (pinfunction "2_2") (pintype "passive"))
      (node (ref "R4") (pin "2") (pinfunction "2_2") (pintype "passive"))
      (node (ref "U1") (pin "3") (pinfunction "VREG5_3") (pintype "passive"))
    )
    (net (code "17") (name "Net-(U2-BST)") (class "Default")
      (node (ref "C8") (pin "2") (pinfunction "2_2") (pintype "passive"))
      (node (ref "U2") (pin "7") (pinfunction "BST_7") (pintype "passive"))
    )
    (net (code "18") (name "Net-(U2-EN)") (class "Default")
      (node (ref "R106") (pin "2") (pinfunction "2_2") (pintype "passive"))
      (node (ref "R5") (pin "1") (pinfunction "1_1") (pintype "passive"))
      (node (ref "U2") (pin "1") (pinfunction "EN_1") (pintype "passive"))
    )
    (net (code "19") (name "Net-(U2-PG)") (class "Default")
      (node (ref "R6") (pin "1") (pinfunction "1_1") (pintype "passive"))
      (node (ref "U2") (pin "4") (pinfunction "PG_4") (pintype "passive"))
    )
    (net (code "20") (name "Net-(U2-SW)") (class "Default")
      (node (ref "C8") (pin "1") (pinfunction "1_1") (pintype "passive"))
      (node (ref "L2") (pin "1") (pinfunction "1_1") (pintype "passive"))
      (node (ref "U2") (pin "6") (pinfunction "SW_6") (pintype "passive"))
    )
    (net (code "21") (name "Net-(U2-VFB)") (class "Default")
      (node (ref "R7") (pin "2") (pinfunction "2_2") (pintype "passive"))
      (node (ref "R8") (pin "1") (pinfunction "1_1") (pintype "passive"))
      (node (ref "U2") (pin "2") (pinfunction "VFB_2") (pintype "passive"))
    )
    (net (code "22") (name "Net-(U2-VREG5)") (class "Default")
      (node (ref "C10") (pin "2") (pinfunction "2_2") (pintype "passive"))
      (node (ref "R6") (pin "2") (pinfunction "2_2") (pintype "passive"))
      (node (ref "U2") (pin "3") (pinfunction "VREG5_3") (pintype "passive"))
    )
    (net (code "23") (name "Net-(U3-EN)") (class "Default")
      (node (ref "C19") (pin "2") (pinfunction "2_2") (pintype "passive"))
      (node (ref "R10") (pin "1") (pinfunction "1_1") (pintype "passive"))
      (node (ref "R37") (pin "1") (pinfunction "1_1") (pintype "passive"))
      (node (ref "R9") (pin "2") (pinfunction "2_2") (pintype "passive"))
      (node (ref "U3") (pin "3") (pinfunction "EN_3") (pintype "passive"))
    )
    (net (code "24") (name "Net-(U3-SW)") (class "Default")
      (node (ref "L3") (pin "1") (pinfunction "1_1") (pintype "passive"))
      (node (ref "U3") (pin "5") (pinfunction "SW_5") (pintype "passive"))
    )
    (net (code "25") (name "Net-(U3-VIN)") (class "Default")
      (node (ref "R126") (pin "2") (pinfunction "2_2") (pintype "passive"))
      (node (ref "R127") (pin "2") (pinfunction "2_2") (pintype "passive"))
      (node (ref "R9") (pin "1") (pinfunction "1_1") (pintype "passive"))
      (node (ref "U3") (pin "1") (pinfunction "VIN_1") (pintype "passive"))
    )
    (net (code "26") (name "Net-(U8-EN)") (class "Default")
      (node (ref "C152") (pin "2") (pinfunction "2_2") (pintype "passive"))
      (node (ref "R11") (pin "2") (pinfunction "2_2") (pintype "passive"))
      (node (ref "R12") (pin "1") (pinfunction "1_1") (pintype "passive"))
      (node (ref "R63") (pin "1") (pinfunction "1_1") (pintype "passive"))
      (node (ref "U8") (pin "3") (pinfunction "EN_3") (pintype "passive"))
    )
    (net (code "27") (name "Net-(U8-SW)") (class "Default")
      (node (ref "L15") (pin "1") (pinfunction "1_1") (pintype "passive"))
      (node (ref "U8") (pin "5") (pinfunction "SW_5") (pintype "passive"))
    )
    (net (code "28") (name "Net-(U8-VIN)") (class "Default")
      (node (ref "R11") (pin "1") (pinfunction "1_1") (pintype "passive"))
      (node (ref "R128") (pin "2") (pinfunction "2_2") (pintype "passive"))
      (node (ref "R129") (pin "2") (pinfunction "2_2") (pintype "passive"))
      (node (ref "U8") (pin "1") (pinfunction "VIN_1") (pintype "passive"))
    )
    (net (code "29") (name "Net-(U19-LBI)") (class "Default")
      (node (ref "R144") (pin "2") (pinfunction "2_2") (pintype "passive"))
      (node (ref "R145") (pin "1") (pinfunction "1_1") (pintype "passive"))
      (node (ref "U19") (pin "9") (pinfunction "LBI_9") (pintype "passive"))
    )
    (net (code "30") (name "Net-(U19-LBO)") (class "Default")
      (node (ref "R130") (pin "1") (pinfunction "1_1") (pintype "passive"))
      (node (ref "U19") (pin "12") (pinfunction "LBO_12") (pintype "passive"))
    )
    (net (code "31") (name "Net-(U19-SW1)") (class "Default")
      (node (ref "L16") (pin "2") (pinfunction "2_2") (pintype "passive"))
      (node (ref "U19") (pin "3") (pinfunction "SW1_3") (pintype "passive"))
      (node (ref "U19") (pin "4") (pinfunction "SW2_4") (pintype "passive"))
    )
    (net (code "32") (name "Net-(U19-SYNC)") (class "Default")
      (node (ref "R146") (pin "2") (pinfunction "2_2") (pintype "passive"))
      (node (ref "R147") (pin "1") (pinfunction "1_1") (pintype "passive"))
      (node (ref "U19") (pin "10") (pinfunction "SYNC_10") (pintype "passive"))
    )
    (net (code "33") (name "VCC_3.3V1") (class "Default")
      (node (ref "C20") (pin "2") (pinfunction "2_2") (pintype "passive"))
      (node (ref "C9") (pin "2") (pinfunction "2_2") (pintype "passive"))
      (node (ref "FB4") (pin "1") (pinfunction "1_1") (pintype "passive"))
      (node (ref "FB6") (pin "1") (pinfunction "1_1") (pintype "passive"))
      (node (ref "L3") (pin "2") (pinfunction "2_2") (pintype "passive"))
      (node (ref "U3") (pin "4") (pinfunction "FB_4") (pintype "passive"))
    )
    (net (code "34") (name "VCC_3.3V2") (class "Default")
      (node (ref "C21") (pin "2") (pinfunction "2_2") (pintype "passive"))
      (node (ref "L15") (pin "2") (pinfunction "2_2") (pintype "passive"))
      (node (ref "U8") (pin "4") (pinfunction "FB_4") (pintype "passive"))
    )
    (net (code "35") (name "VCC_4.2V") (class "Default")
      (node (ref "C11") (pin "2") (pinfunction "2_2") (pintype "passive"))
      (node (ref "C12") (pin "2") (pinfunction "2_2") (pintype "passive"))
      (node (ref "L2") (pin "2") (pinfunction "2_2") (pintype "passive"))
      (node (ref "R7") (pin "1") (pinfunction "1_1") (pintype "passive"))
      (node (ref "RN2") (pin "2") (pinfunction "2_2") (pintype "passive"))
    )
    (net (code "36") (name "VCC_5V") (class "Default")
      (node (ref "C51") (pin "2") (pinfunction "2_2") (pintype "passive"))
      (node (ref "C6") (pin "2") (pinfunction "2_2") (pintype "passive"))
      (node (ref "C7") (pin "2") (pinfunction "2_2") (pintype "passive"))
      (node (ref "L1") (pin "2") (pinfunction "2_2") (pintype "passive"))
      (node (ref "R1") (pin "1") (pinfunction "1_1") (pintype "passive"))
      (node (ref "R126") (pin "1") (pinfunction "1_1") (pintype "passive"))
      (node (ref "R128") (pin "1") (pinfunction "1_1") (pintype "passive"))
      (node (ref "R5") (pin "2") (pinfunction "2_2") (pintype "passive"))
      (node (ref "RN1") (pin "2") (pinfunction "2_2") (pintype "passive"))
      (node (ref "U2") (pin "8") (pinfunction "VIN_8") (pintype "passive"))
    )
    (net (code "37") (name "VCC_USB") (class "Default")
      (node (ref "C153") (pin "2") (pinfunction "2_2") (pintype "passive"))
      (node (ref "C154") (pin "2") (pinfunction "2_2") (pintype "passive"))
      (node (ref "C50") (pin "2") (pinfunction "2_2") (pintype "passive"))
      (node (ref "R130") (pin "2") (pinfunction "2_2") (pintype "passive"))
      (node (ref "U19") (pin "1") (pinfunction "VOU1_1") (pintype "passive"))
      (node (ref "U19") (pin "15") (pinfunction "VOUT2_15") (pintype "passive"))
      (node (ref "U19") (pin "16") (pinfunction "VOU3_16") (pintype "passive"))
    )
    (net (code "38") (name "VDD_BLE") (class "Default")
      (node (ref "C17") (pin "1") (pinfunction "1_1") (pintype "passive"))
      (node (ref "FB5") (pin "2") (pinfunction "2_2") (pintype "passive"))
    )
    (net (code "39") (name "VDD_ZB") (class "Default")
      (node (ref "C13") (pin "2") (pinfunction "2_2") (pintype "passive"))
      (node (ref "FB4") (pin "2") (pinfunction "2_2") (pintype "passive"))
    )
    (net (code "40") (name "VDD_ZWAVE") (class "Default")
      (node (ref "C18") (pin "1") (pinfunction "1_1") (pintype "passive"))
      (node (ref "FB6") (pin "2") (pinfunction "2_2") (pintype "passive"))
    )
    (net (code "41") (name "V_SYS") (class "Default")
      (node (ref "C155") (pin "2") (pinfunction "2_2") (pintype "passive"))
      (node (ref "L16") (pin "1") (pinfunction "1_1") (pintype "passive"))
      (node (ref "Q1") (pin "2") (pinfunction "E_2") (pintype "passive"))
      (node (ref "R127") (pin "1") (pinfunction "1_1") (pintype "passive"))
      (node (ref "R129") (pin "1") (pinfunction "1_1") (pintype "passive"))
      (node (ref "R144") (pin "1") (pinfunction "1_1") (pintype "passive"))
      (node (ref "R146") (pin "1") (pinfunction "1_1") (pintype "passive"))
      (node (ref "R27") (pin "1") (pinfunction "1_1") (pintype "passive"))
      (node (ref "RN2") (pin "1") (pinfunction "1_1") (pintype "passive"))
      (node (ref "U19") (pin "8") (pinfunction "VBAT_8") (pintype "passive"))
    )
    (net (code "42") (name "unconnected-(FB5-Pad1)") (class "Default")
      (node (ref "FB5") (pin "1") (pinfunction "1_1") (pintype "passive"))
    )
    (net (code "43") (name "unconnected-(J1-S-Pad3)") (class "Default")
      (node (ref "J1") (pin "3") (pinfunction "S_3") (pintype "power_in"))
    )
    (net (code "44") (name "unconnected-(SH4-Pad2)") (class "Default")
      (node (ref "SH4") (pin "2") (pinfunction "2_2") (pintype "passive"))
    )
    (net (code "45") (name "unconnected-(U19-FB-Pad14)") (class "Default")
      (node (ref "U19") (pin "14") (pinfunction "FB_14") (pintype "passive"))
    )
    (net (code "46") (name "unconnected-(U19-NC-Pad2)") (class "Default")
      (node (ref "U19") (pin "2") (pinfunction "NC_2") (pintype "passive"))
    )
  )
)
